# MySTM32F103C8.net
KiCad netlist of a schematic drawn in Altium Designer
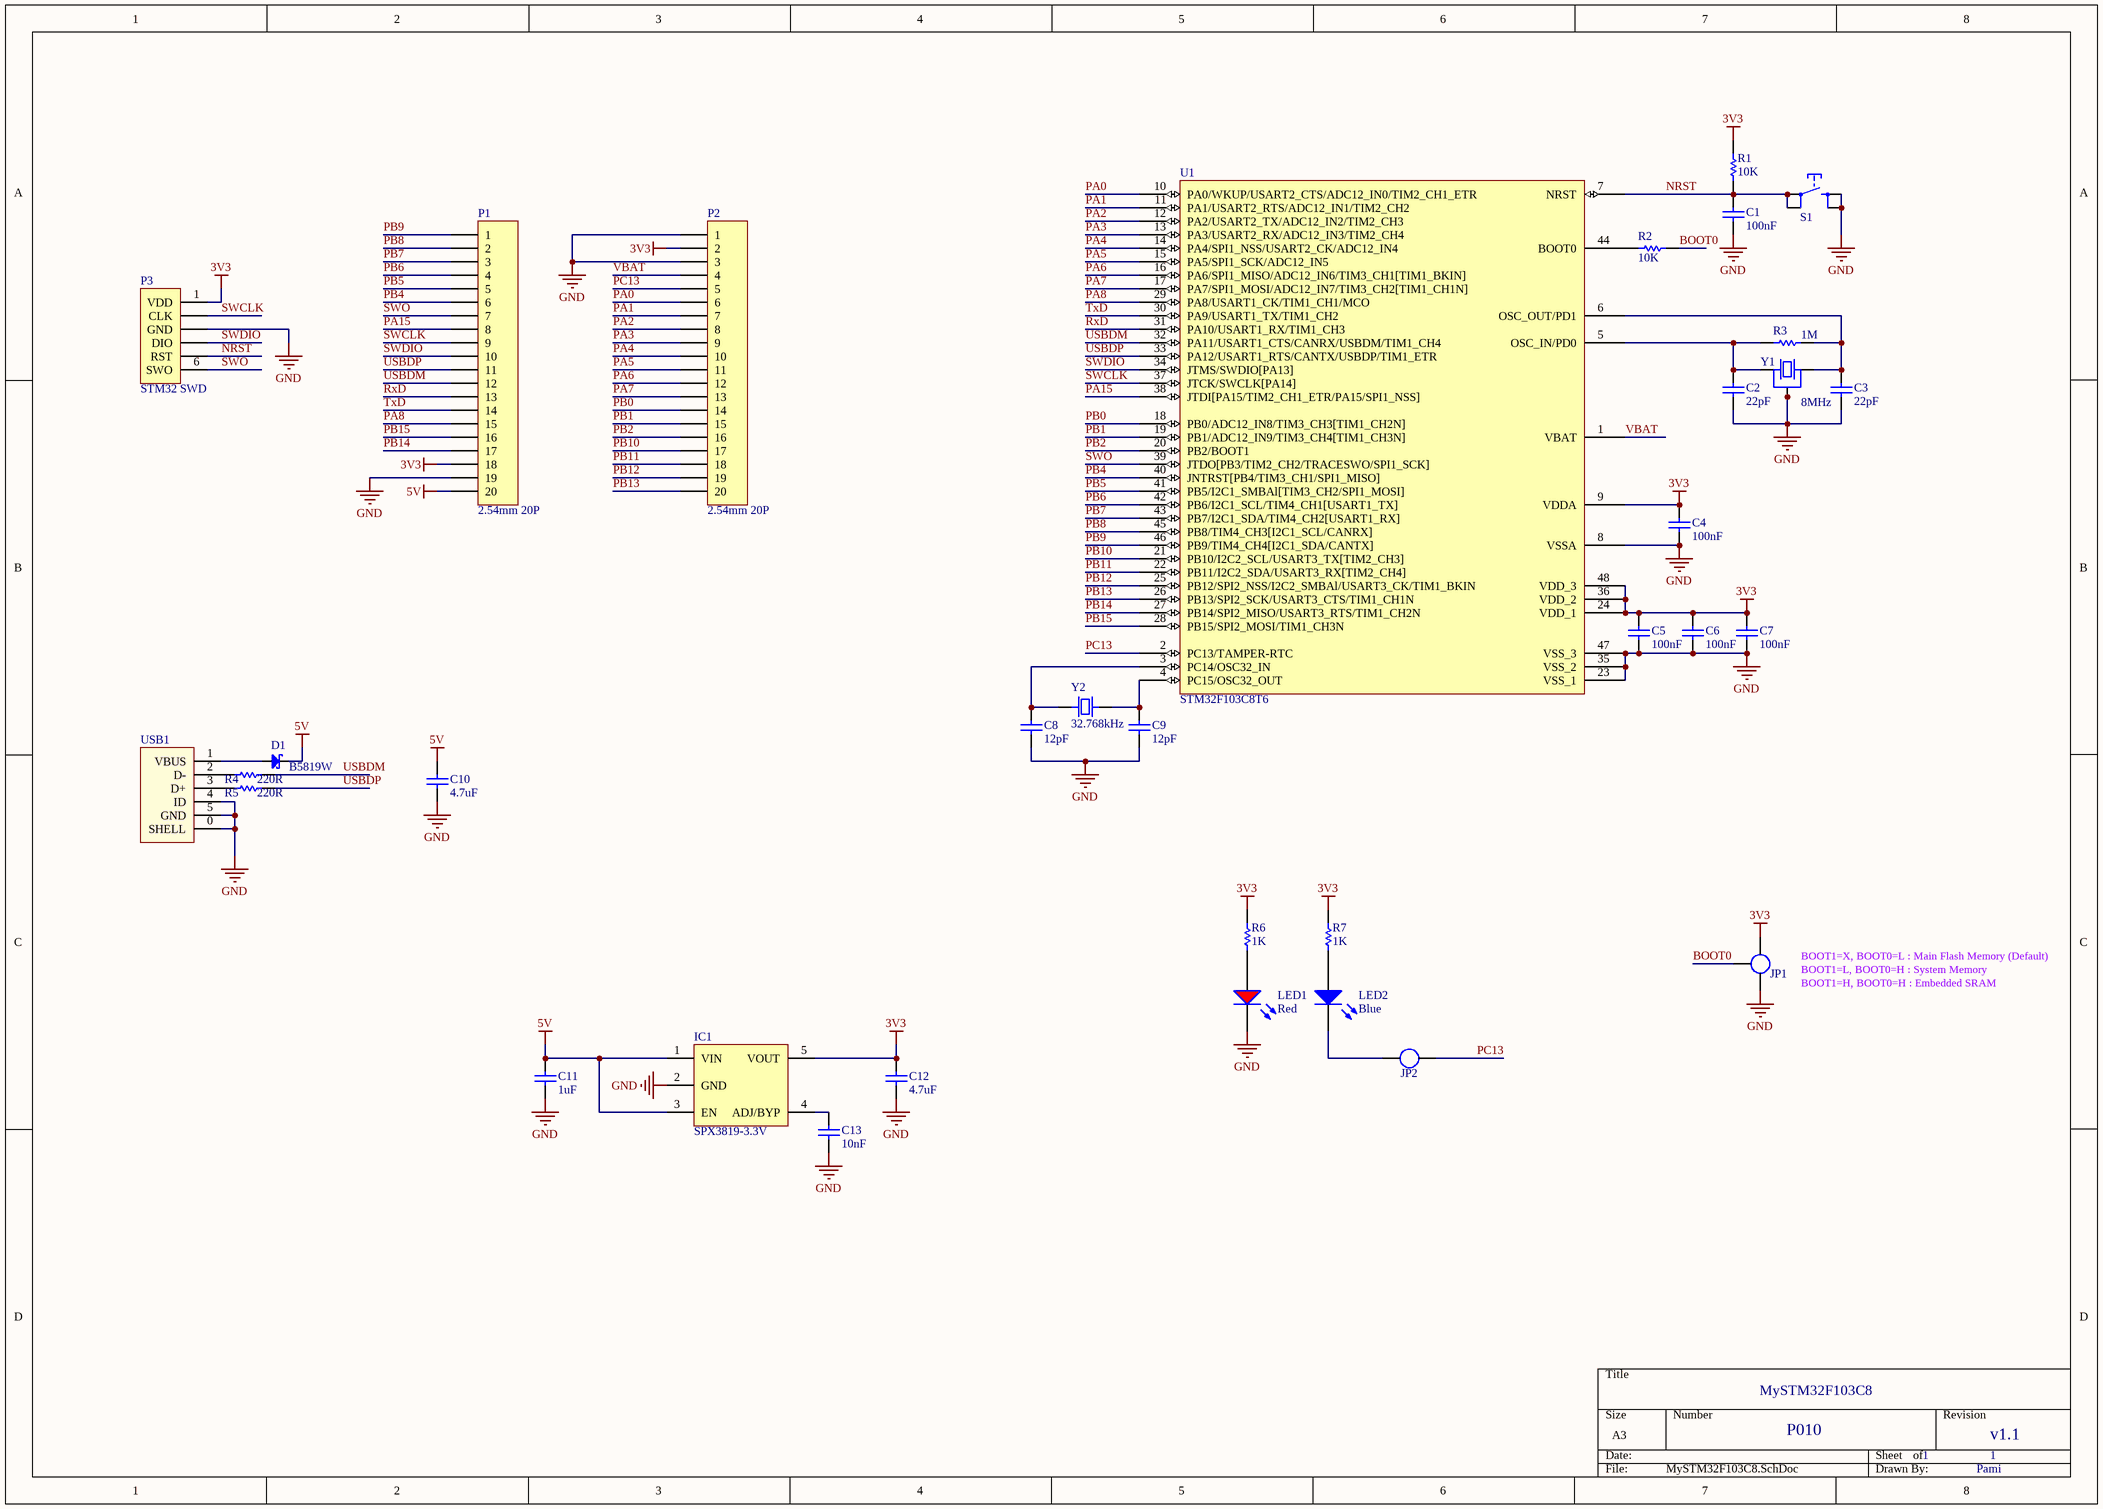
[diagram p0: MySTM32F103C8.SchDoc]

(export (version "E")
  (design (tool "Eeschema 10.0.6"))
  (components
    (comp (ref "C1")
      (value "100nF")
      (footprint "SMD-CAP-0402")
      (description "贴片电容")
      (fields
        (field (name "TOLERANCE") "±10%")
        (field (name "MANUFACTURER") "FengHua, YAGEO, Samsung, TDK, Murata")
      )
      (libsource (lib "My Capacitors") (part "0402 100nF (104) 10% 16V X7R"))
    )
    (comp (ref "C2")
      (value "22pF")
      (footprint "SMD-CAP-0402")
      (description "贴片电容")
      (fields
        (field (name "TOLERANCE") "±5%")
        (field (name "MANUFACTURER") "FengHua, YAGEO, Samsung, TDK, Murata")
      )
      (libsource (lib "My Capacitors") (part "0402 22pF (220) 5% 50V COG"))
    )
    (comp (ref "C3")
      (value "22pF")
      (footprint "SMD-CAP-0402")
      (description "贴片电容")
      (fields
        (field (name "TOLERANCE") "±5%")
        (field (name "MANUFACTURER") "FengHua, YAGEO, Samsung, TDK, Murata")
      )
      (libsource (lib "My Capacitors") (part "0402 22pF (220) 5% 50V COG"))
    )
    (comp (ref "C4")
      (value "100nF")
      (footprint "SMD-CAP-0402")
      (description "贴片电容")
      (fields
        (field (name "TOLERANCE") "±10%")
        (field (name "MANUFACTURER") "FengHua, YAGEO, Samsung, TDK, Murata")
      )
      (libsource (lib "My Capacitors") (part "0402 100nF (104) 10% 16V X7R"))
    )
    (comp (ref "C5")
      (value "100nF")
      (footprint "SMD-CAP-0402")
      (description "贴片电容")
      (fields
        (field (name "TOLERANCE") "±10%")
        (field (name "MANUFACTURER") "FengHua, YAGEO, Samsung, TDK, Murata")
      )
      (libsource (lib "My Capacitors") (part "0402 100nF (104) 10% 16V X7R"))
    )
    (comp (ref "C6")
      (value "100nF")
      (footprint "SMD-CAP-0402")
      (description "贴片电容")
      (fields
        (field (name "TOLERANCE") "±10%")
        (field (name "MANUFACTURER") "FengHua, YAGEO, Samsung, TDK, Murata")
      )
      (libsource (lib "My Capacitors") (part "0402 100nF (104) 10% 16V X7R"))
    )
    (comp (ref "C7")
      (value "100nF")
      (footprint "SMD-CAP-0402")
      (description "贴片电容")
      (fields
        (field (name "TOLERANCE") "±10%")
        (field (name "MANUFACTURER") "FengHua, YAGEO, Samsung, TDK, Murata")
      )
      (libsource (lib "My Capacitors") (part "0402 100nF (104) 10% 16V X7R"))
    )
    (comp (ref "C8")
      (value "12pF")
      (footprint "SMD-CAP-0402")
      (description "贴片电容")
      (fields
        (field (name "TOLERANCE") "±5%")
        (field (name "MANUFACTURER") "FengHua, YAGEO, Samsung, TDK, Murata")
      )
      (libsource (lib "My Capacitors") (part "0402 12pF (120) 5% 50V COG"))
    )
    (comp (ref "C9")
      (value "12pF")
      (footprint "SMD-CAP-0402")
      (description "贴片电容")
      (fields
        (field (name "TOLERANCE") "±5%")
        (field (name "MANUFACTURER") "FengHua, YAGEO, Samsung, TDK, Murata")
      )
      (libsource (lib "My Capacitors") (part "0402 12pF (120) 5% 50V COG"))
    )
    (comp (ref "C10")
      (value "4.7uF")
      (footprint "SMD-CAP-0603")
      (description "贴片电容")
      (fields
        (field (name "TOLERANCE") "±10%")
        (field (name "MANUFACTURER") "FengHua, YAGEO, Samsung, TDK, Murata")
      )
      (libsource (lib "My Capacitors") (part "0603 4.7uF (475) 10% 10V X5R"))
    )
    (comp (ref "C11")
      (value "1uF")
      (footprint "SMD-CAP-0402")
      (description "贴片电容")
      (fields
        (field (name "TOLERANCE") "±10%")
        (field (name "MANUFACTURER") "FengHua, YAGEO, Samsung, TDK, Murata")
      )
      (libsource (lib "My Capacitors") (part "0402 1uF(105) 10% 16V X5R"))
    )
    (comp (ref "C12")
      (value "4.7uF")
      (footprint "SMD-CAP-0603")
      (description "贴片电容")
      (fields
        (field (name "TOLERANCE") "±10%")
        (field (name "MANUFACTURER") "FengHua, YAGEO, Samsung, TDK, Murata")
      )
      (libsource (lib "My Capacitors") (part "0603 4.7uF (475) 10% 10V X5R"))
    )
    (comp (ref "C13")
      (value "10nF")
      (footprint "SMD-CAP-0402")
      (description "贴片电容")
      (fields
        (field (name "TOLERANCE") "±10%")
        (field (name "MANUFACTURER") "FengHua, YAGEO, Samsung, TDK, Murata")
      )
      (libsource (lib "My Capacitors") (part "0402 10nF (103) 10% 50V X7R"))
    )
    (comp (ref "D1")
      (value "B5819W")
      (footprint "SOD-123")
      (description "贴片二极管")
      (libsource (lib "My Diodes") (part "B5819W 40V/1A"))
    )
    (comp (ref "IC1")
      (value "SPX3819-3.3V")
      (footprint "SOT-23-5")
      (description "贴片LDO")
      (fields (field (name "MANUFACTURER") "EXAR") (field (name "TOLERANCE") "1%"))
      (libsource (lib "My LDO") (part "SPX3819M5 3.3V 500mA"))
    )
    (comp (ref "JP1")
      (value "JP-3P-P")
      (footprint "SMD-JUMPER-3-PASTE")
      (libsource (lib "My Jumpers") (part "JP-3P-P"))
    )
    (comp (ref "JP2")
      (value "JP-2P-P")
      (footprint "SMD-JUMPER-2-PASTE")
      (libsource (lib "My Jumpers") (part "JP-2P-P"))
    )
    (comp (ref "LED1")
      (value "Red")
      (footprint "SMD-LED-0603-RED")
      (description "贴片LED")
      (libsource (lib "My LED") (part "0603 Red"))
    )
    (comp (ref "LED2")
      (value "Blue")
      (footprint "SMD-LED-0603-BLUE")
      (description "贴片LED")
      (libsource (lib "My LED") (part "0603 Blue"))
    )
    (comp (ref "P1")
      (value "2.54mm 20P")
      (footprint "PSH1x20")
      (description "直插式连接器 2.54mm")
      (libsource (lib "My Connectors") (part "PSH Header 2.54mm 20P"))
    )
    (comp (ref "P2")
      (value "2.54mm 20P")
      (footprint "PSH1x20")
      (description "直插式连接器 2.54mm")
      (libsource (lib "My Connectors") (part "PSH Header 2.54mm 20P"))
    )
    (comp (ref "P3")
      (value "STM32 SWD")
      (footprint "STM32-SWD-PTH-6-2.45")
      (description "调试端口")
      (libsource (lib "My Connectors") (part "STM32 SWD6 PTH 2.54mm"))
    )
    (comp (ref "R1")
      (value "10K")
      (footprint "SMD-RES-0402")
      (description "贴片电阻")
      (fields
        (field (name "MANUFACTURER") "FengHua, YAGEO, RALEC, KOA, ROHM")
        (field (name "TOLERANCE") "±1%")
      )
      (libsource (lib "My Resistors") (part "0402 10KΩ (1002) 1% 1/16W"))
    )
    (comp (ref "R2")
      (value "10K")
      (footprint "SMD-RES-0402")
      (description "贴片电阻")
      (fields
        (field (name "MANUFACTURER") "FengHua, YAGEO, RALEC, KOA, ROHM")
        (field (name "TOLERANCE") "±1%")
      )
      (libsource (lib "My Resistors") (part "0402 10KΩ (1002) 1% 1/16W"))
    )
    (comp (ref "R3")
      (value "1M")
      (footprint "SMD-RES-0402")
      (description "贴片电阻")
      (fields
        (field (name "MANUFACTURER") "FengHua, YAGEO, RALEC, KOA, ROHM")
        (field (name "TOLERANCE") "±1%")
      )
      (libsource (lib "My Resistors") (part "0402 1MΩ (1004) 1% 1/16W"))
    )
    (comp (ref "R4")
      (value "220R")
      (footprint "SMD-RES-0402")
      (description "贴片电阻")
      (fields
        (field (name "MANUFACTURER") "FengHua, YAGEO, RALEC, KOA, ROHM")
        (field (name "TOLERANCE") "±1%")
      )
      (libsource (lib "My Resistors") (part "0402 220Ω (2200) 1% 1/16W"))
    )
    (comp (ref "R5")
      (value "220R")
      (footprint "SMD-RES-0402")
      (description "贴片电阻")
      (fields
        (field (name "MANUFACTURER") "FengHua, YAGEO, RALEC, KOA, ROHM")
        (field (name "TOLERANCE") "±1%")
      )
      (libsource (lib "My Resistors") (part "0402 220Ω (2200) 1% 1/16W"))
    )
    (comp (ref "R6")
      (value "1K")
      (footprint "SMD-RES-0402")
      (description "贴片电阻")
      (fields
        (field (name "MANUFACTURER") "FengHua, YAGEO, RALEC, KOA, ROHM")
        (field (name "TOLERANCE") "±1%")
      )
      (libsource (lib "My Resistors") (part "0402 1KΩ (1001) 1% 1/16W"))
    )
    (comp (ref "R7")
      (value "1K")
      (footprint "SMD-RES-0402")
      (description "贴片电阻")
      (fields
        (field (name "MANUFACTURER") "FengHua, YAGEO, RALEC, KOA, ROHM")
        (field (name "TOLERANCE") "±1%")
      )
      (libsource (lib "My Resistors") (part "0402 1KΩ (1001) 1% 1/16W"))
    )
    (comp (ref "S1")
      (value "Tact Switch 4x4")
      (footprint "SMD-SW-4x4")
      (description "轻触开关")
      (libsource (lib "My TactSwitch") (part "Tact Switch 4x4"))
    )
    (comp (ref "U1")
      (value "STM32F103C8T6")
      (footprint "LQFP48")
      (description "贴片 STM32 MCU")
      (libsource (lib "My Microcontrollers") (part "STM32F103C8T6"))
    )
    (comp (ref "USB1")
      (value "MicroUSB")
      (footprint "MICRO-USB-5P4S")
      (description "贴片USB母座")
      (fields (field (name "PART NUMBER") "614105150721") (field (name "PUBLISHER") "Wurth Elektronik"))
      (libsource (lib "My USB") (part "MicroUSB 5P 无卷边"))
    )
    (comp (ref "Y1")
      (value "8MHz")
      (footprint "OSC-3225")
      (description "贴片无源晶振")
      (libsource (lib "My Crystal oscillator") (part "3225 8MHz ±10ppm 10pF"))
    )
    (comp (ref "Y2")
      (value "32.768kHz")
      (footprint "OSC-FC-135")
      (description "贴片晶振")
      (fields (field (name "MANUFACTURER") "EPSON"))
      (libsource (lib "My Crystal oscillator") (part "3215 32.768kHz ±20ppm 12.5pF"))
    )
  )
  (nets
    (net (code "1") (name "/BOOT0") (class "Default")
      (node (ref "JP1") (pin "2") (pinfunction "2_2") (pintype "passive"))
      (node (ref "R2") (pin "1") (pinfunction "1_1") (pintype "passive"))
    )
    (net (code "2") (name "/NRST") (class "Default")
      (node (ref "C1") (pin "2") (pinfunction "2_2") (pintype "passive"))
      (node (ref "P3") (pin "5") (pinfunction "RST_5") (pintype "passive"))
      (node (ref "R1") (pin "1") (pinfunction "1_1") (pintype "passive"))
      (node (ref "S1") (pin "1") (pinfunction "1_1") (pintype "passive"))
      (node (ref "S1") (pin "2") (pinfunction "2_2") (pintype "passive"))
      (node (ref "U1") (pin "7") (pinfunction "NRST_7") (pintype "bidirectional"))
    )
    (net (code "3") (name "/PA0") (class "Default")
      (node (ref "P2") (pin "6") (pinfunction "6_6") (pintype "passive"))
      (node (ref "U1") (pin "10") (pinfunction "PA0/WKUP/USART2_CTS/ADC12_IN0/TIM2_CH1_ETR_10") (pintype "bidirectional"))
    )
    (net (code "4") (name "/PA1") (class "Default")
      (node (ref "P2") (pin "7") (pinfunction "7_7") (pintype "passive"))
      (node (ref "U1") (pin "11") (pinfunction "PA1/USART2_RTS/ADC12_IN1/TIM2_CH2_11") (pintype "bidirectional"))
    )
    (net (code "5") (name "/PA2") (class "Default")
      (node (ref "P2") (pin "8") (pinfunction "8_8") (pintype "passive"))
      (node (ref "U1") (pin "12") (pinfunction "PA2/USART2_TX/ADC12_IN2/TIM2_CH3_12") (pintype "bidirectional"))
    )
    (net (code "6") (name "/PA3") (class "Default")
      (node (ref "P2") (pin "9") (pinfunction "9_9") (pintype "passive"))
      (node (ref "U1") (pin "13") (pinfunction "PA3/USART2_RX/ADC12_IN3/TIM2_CH4_13") (pintype "bidirectional"))
    )
    (net (code "7") (name "/PA4") (class "Default")
      (node (ref "P2") (pin "10") (pinfunction "10_10") (pintype "passive"))
      (node (ref "U1") (pin "14") (pinfunction "PA4/SPI1_NSS/USART2_CK/ADC12_IN4_14") (pintype "bidirectional"))
    )
    (net (code "8") (name "/PA5") (class "Default")
      (node (ref "P2") (pin "11") (pinfunction "11_11") (pintype "passive"))
      (node (ref "U1") (pin "15") (pinfunction "PA5/SPI1_SCK/ADC12_IN5_15") (pintype "bidirectional"))
    )
    (net (code "9") (name "/PA6") (class "Default")
      (node (ref "P2") (pin "12") (pinfunction "12_12") (pintype "passive"))
      (node (ref "U1") (pin "16") (pinfunction "PA6/SPI1_MISO/ADC12_IN6/TIM3_CH1[TIM1_BKIN]_16") (pintype "bidirectional"))
    )
    (net (code "10") (name "/PA7") (class "Default")
      (node (ref "P2") (pin "13") (pinfunction "13_13") (pintype "passive"))
      (node (ref "U1") (pin "17") (pinfunction "PA7/SPI1_MOSI/ADC12_IN7/TIM3_CH2[TIM1_CH1N]_17") (pintype "bidirectional"))
    )
    (net (code "11") (name "/PA8") (class "Default")
      (node (ref "P1") (pin "15") (pinfunction "15_15") (pintype "passive"))
      (node (ref "U1") (pin "29") (pinfunction "PA8/USART1_CK/TIM1_CH1/MCO_29") (pintype "bidirectional"))
    )
    (net (code "12") (name "/PA15") (class "Default")
      (node (ref "P1") (pin "8") (pinfunction "8_8") (pintype "passive"))
      (node (ref "U1") (pin "38") (pinfunction "JTDI[PA15/TIM2_CH1_ETR/PA15/SPI1_NSS]_38") (pintype "bidirectional"))
    )
    (net (code "13") (name "/PB0") (class "Default")
      (node (ref "P2") (pin "14") (pinfunction "14_14") (pintype "passive"))
      (node (ref "U1") (pin "18") (pinfunction "PB0/ADC12_IN8/TIM3_CH3[TIM1_CH2N]_18") (pintype "bidirectional"))
    )
    (net (code "14") (name "/PB1") (class "Default")
      (node (ref "P2") (pin "15") (pinfunction "15_15") (pintype "passive"))
      (node (ref "U1") (pin "19") (pinfunction "PB1/ADC12_IN9/TIM3_CH4[TIM1_CH3N]_19") (pintype "bidirectional"))
    )
    (net (code "15") (name "/PB2") (class "Default")
      (node (ref "P2") (pin "16") (pinfunction "16_16") (pintype "passive"))
      (node (ref "U1") (pin "20") (pinfunction "PB2/BOOT1_20") (pintype "bidirectional"))
    )
    (net (code "16") (name "/PB4") (class "Default")
      (node (ref "P1") (pin "6") (pinfunction "6_6") (pintype "passive"))
      (node (ref "U1") (pin "40") (pinfunction "JNTRST[PB4/TIM3_CH1/SPI1_MISO]_40") (pintype "bidirectional"))
    )
    (net (code "17") (name "/PB5") (class "Default")
      (node (ref "P1") (pin "5") (pinfunction "5_5") (pintype "passive"))
      (node (ref "U1") (pin "41") (pinfunction "PB5/I2C1_SMBAl[TIM3_CH2/SPI1_MOSI]_41") (pintype "bidirectional"))
    )
    (net (code "18") (name "/PB6") (class "Default")
      (node (ref "P1") (pin "4") (pinfunction "4_4") (pintype "passive"))
      (node (ref "U1") (pin "42") (pinfunction "PB6/I2C1_SCL/TIM4_CH1[USART1_TX]_42") (pintype "bidirectional"))
    )
    (net (code "19") (name "/PB7") (class "Default")
      (node (ref "P1") (pin "3") (pinfunction "3_3") (pintype "passive"))
      (node (ref "U1") (pin "43") (pinfunction "PB7/I2C1_SDA/TIM4_CH2[USART1_RX]_43") (pintype "bidirectional"))
    )
    (net (code "20") (name "/PB8") (class "Default")
      (node (ref "P1") (pin "2") (pinfunction "2_2") (pintype "passive"))
      (node (ref "U1") (pin "45") (pinfunction "PB8/TIM4_CH3[I2C1_SCL/CANRX]_45") (pintype "bidirectional"))
    )
    (net (code "21") (name "/PB9") (class "Default")
      (node (ref "P1") (pin "1") (pinfunction "1_1") (pintype "passive"))
      (node (ref "U1") (pin "46") (pinfunction "PB9/TIM4_CH4[I2C1_SDA/CANTX]_46") (pintype "bidirectional"))
    )
    (net (code "22") (name "/PB10") (class "Default")
      (node (ref "P2") (pin "17") (pinfunction "17_17") (pintype "passive"))
      (node (ref "U1") (pin "21") (pinfunction "PB10/I2C2_SCL/USART3_TX[TIM2_CH3]_21") (pintype "bidirectional"))
    )
    (net (code "23") (name "/PB11") (class "Default")
      (node (ref "P2") (pin "18") (pinfunction "18_18") (pintype "passive"))
      (node (ref "U1") (pin "22") (pinfunction "PB11/I2C2_SDA/USART3_RX[TIM2_CH4]_22") (pintype "bidirectional"))
    )
    (net (code "24") (name "/PB12") (class "Default")
      (node (ref "P2") (pin "19") (pinfunction "19_19") (pintype "passive"))
      (node (ref "U1") (pin "25") (pinfunction "PB12/SPI2_NSS/I2C2_SMBAl/USART3_CK/TIM1_BKIN_25") (pintype "bidirectional"))
    )
    (net (code "25") (name "/PB13") (class "Default")
      (node (ref "P2") (pin "20") (pinfunction "20_20") (pintype "passive"))
      (node (ref "U1") (pin "26") (pinfunction "PB13/SPI2_SCK/USART3_CTS/TIM1_CH1N_26") (pintype "bidirectional"))
    )
    (net (code "26") (name "/PB14") (class "Default")
      (node (ref "P1") (pin "17") (pinfunction "17_17") (pintype "passive"))
      (node (ref "U1") (pin "27") (pinfunction "PB14/SPI2_MISO/USART3_RTS/TIM1_CH2N_27") (pintype "bidirectional"))
    )
    (net (code "27") (name "/PB15") (class "Default")
      (node (ref "P1") (pin "16") (pinfunction "16_16") (pintype "passive"))
      (node (ref "U1") (pin "28") (pinfunction "PB15/SPI2_MOSI/TIM1_CH3N_28") (pintype "bidirectional"))
    )
    (net (code "28") (name "/PC13") (class "Default")
      (node (ref "JP2") (pin "2") (pinfunction "2_2") (pintype "passive"))
      (node (ref "P2") (pin "5") (pinfunction "5_5") (pintype "passive"))
      (node (ref "U1") (pin "2") (pinfunction "PC13/TAMPER-RTC_2") (pintype "bidirectional"))
    )
    (net (code "29") (name "/RxD") (class "Default")
      (node (ref "P1") (pin "13") (pinfunction "13_13") (pintype "passive"))
      (node (ref "U1") (pin "31") (pinfunction "PA10/USART1_RX/TIM1_CH3_31") (pintype "bidirectional"))
    )
    (net (code "30") (name "/SWCLK") (class "Default")
      (node (ref "P1") (pin "9") (pinfunction "9_9") (pintype "passive"))
      (node (ref "P3") (pin "2") (pinfunction "CLK_2") (pintype "passive"))
      (node (ref "U1") (pin "37") (pinfunction "JTCK/SWCLK[PA14]_37") (pintype "bidirectional"))
    )
    (net (code "31") (name "/SWDIO") (class "Default")
      (node (ref "P1") (pin "10") (pinfunction "10_10") (pintype "passive"))
      (node (ref "P3") (pin "4") (pinfunction "DIO_4") (pintype "power_in"))
      (node (ref "U1") (pin "34") (pinfunction "JTMS/SWDIO[PA13]_34") (pintype "bidirectional"))
    )
    (net (code "32") (name "/SWO") (class "Default")
      (node (ref "P1") (pin "7") (pinfunction "7_7") (pintype "passive"))
      (node (ref "P3") (pin "6") (pinfunction "SWO_6") (pintype "passive"))
      (node (ref "U1") (pin "39") (pinfunction "JTDO[PB3/TIM2_CH2/TRACESWO/SPI1_SCK]_39") (pintype "bidirectional"))
    )
    (net (code "33") (name "/TxD") (class "Default")
      (node (ref "P1") (pin "14") (pinfunction "14_14") (pintype "passive"))
      (node (ref "U1") (pin "30") (pinfunction "PA9/USART1_TX/TIM1_CH2_30") (pintype "bidirectional"))
    )
    (net (code "34") (name "/USBDM") (class "Default")
      (node (ref "P1") (pin "12") (pinfunction "12_12") (pintype "passive"))
      (node (ref "R4") (pin "2") (pinfunction "2_2") (pintype "passive"))
      (node (ref "U1") (pin "32") (pinfunction "PA11/USART1_CTS/CANRX/USBDM/TIM1_CH4_32") (pintype "bidirectional"))
    )
    (net (code "35") (name "/USBDP") (class "Default")
      (node (ref "P1") (pin "11") (pinfunction "11_11") (pintype "passive"))
      (node (ref "R5") (pin "2") (pinfunction "2_2") (pintype "passive"))
      (node (ref "U1") (pin "33") (pinfunction "PA12/USART1_RTS/CANTX/USBDP/TIM1_ETR_33") (pintype "bidirectional"))
    )
    (net (code "36") (name "/VBAT") (class "Default")
      (node (ref "P2") (pin "4") (pinfunction "4_4") (pintype "passive"))
      (node (ref "U1") (pin "1") (pinfunction "VBAT_1") (pintype "power_in"))
    )
    (net (code "37") (name "3V3") (class "Default")
      (node (ref "C12") (pin "2") (pinfunction "2_2") (pintype "passive"))
      (node (ref "C4") (pin "2") (pinfunction "2_2") (pintype "passive"))
      (node (ref "C5") (pin "2") (pinfunction "2_2") (pintype "passive"))
      (node (ref "C6") (pin "2") (pinfunction "2_2") (pintype "passive"))
      (node (ref "C7") (pin "2") (pinfunction "2_2") (pintype "passive"))
      (node (ref "IC1") (pin "5") (pinfunction "VOUT_5") (pintype "power_in"))
      (node (ref "JP1") (pin "1") (pinfunction "1_1") (pintype "passive"))
      (node (ref "P1") (pin "18") (pinfunction "18_18") (pintype "passive"))
      (node (ref "P2") (pin "2") (pinfunction "2_2") (pintype "passive"))
      (node (ref "P3") (pin "1") (pinfunction "VDD_1") (pintype "power_in"))
      (node (ref "R1") (pin "2") (pinfunction "2_2") (pintype "passive"))
      (node (ref "R6") (pin "2") (pinfunction "2_2") (pintype "passive"))
      (node (ref "R7") (pin "2") (pinfunction "2_2") (pintype "passive"))
      (node (ref "U1") (pin "24") (pinfunction "VDD_1_24") (pintype "power_in"))
      (node (ref "U1") (pin "36") (pinfunction "VDD_2_36") (pintype "power_in"))
      (node (ref "U1") (pin "48") (pinfunction "VDD_3_48") (pintype "power_in"))
      (node (ref "U1") (pin "9") (pinfunction "VDDA_9") (pintype "power_in"))
    )
    (net (code "38") (name "5V") (class "Default")
      (node (ref "C10") (pin "2") (pinfunction "2_2") (pintype "passive"))
      (node (ref "C11") (pin "2") (pinfunction "2_2") (pintype "passive"))
      (node (ref "D1") (pin "1") (pinfunction "K_1") (pintype "passive"))
      (node (ref "IC1") (pin "1") (pinfunction "VIN_1") (pintype "power_in"))
      (node (ref "IC1") (pin "3") (pinfunction "EN_3") (pintype "passive"))
      (node (ref "P1") (pin "20") (pinfunction "20_20") (pintype "passive"))
    )
    (net (code "39") (name "GND") (class "Default")
      (node (ref "C1") (pin "1") (pinfunction "1_1") (pintype "passive"))
      (node (ref "C10") (pin "1") (pinfunction "1_1") (pintype "passive"))
      (node (ref "C11") (pin "1") (pinfunction "1_1") (pintype "passive"))
      (node (ref "C12") (pin "1") (pinfunction "1_1") (pintype "passive"))
      (node (ref "C13") (pin "1") (pinfunction "1_1") (pintype "passive"))
      (node (ref "C2") (pin "1") (pinfunction "1_1") (pintype "passive"))
      (node (ref "C3") (pin "1") (pinfunction "1_1") (pintype "passive"))
      (node (ref "C4") (pin "1") (pinfunction "1_1") (pintype "passive"))
      (node (ref "C5") (pin "1") (pinfunction "1_1") (pintype "passive"))
      (node (ref "C6") (pin "1") (pinfunction "1_1") (pintype "passive"))
      (node (ref "C7") (pin "1") (pinfunction "1_1") (pintype "passive"))
      (node (ref "C8") (pin "1") (pinfunction "1_1") (pintype "passive"))
      (node (ref "C9") (pin "1") (pinfunction "1_1") (pintype "passive"))
      (node (ref "IC1") (pin "2") (pinfunction "GND_2") (pintype "power_in"))
      (node (ref "JP1") (pin "3") (pinfunction "3_3") (pintype "passive"))
      (node (ref "LED1") (pin "2") (pinfunction "K_2") (pintype "passive"))
      (node (ref "P1") (pin "19") (pinfunction "19_19") (pintype "passive"))
      (node (ref "P2") (pin "1") (pinfunction "1_1") (pintype "passive"))
      (node (ref "P2") (pin "3") (pinfunction "3_3") (pintype "passive"))
      (node (ref "P3") (pin "3") (pinfunction "GND_3") (pintype "passive"))
      (node (ref "S1") (pin "3") (pinfunction "3_3") (pintype "passive"))
      (node (ref "S1") (pin "4") (pinfunction "4_4") (pintype "passive"))
      (node (ref "U1") (pin "23") (pinfunction "VSS_1_23") (pintype "power_in"))
      (node (ref "U1") (pin "35") (pinfunction "VSS_2_35") (pintype "power_in"))
      (node (ref "U1") (pin "47") (pinfunction "VSS_3_47") (pintype "power_in"))
      (node (ref "U1") (pin "8") (pinfunction "VSSA_8") (pintype "power_in"))
      (node (ref "USB1") (pin "0") (pinfunction "SHELL_0") (pintype "passive"))
      (node (ref "USB1") (pin "4") (pinfunction "ID_4") (pintype "passive"))
      (node (ref "USB1") (pin "5") (pinfunction "GND_5") (pintype "passive"))
      (node (ref "Y1") (pin "2") (pinfunction "2_2") (pintype "power_in"))
      (node (ref "Y1") (pin "4") (pinfunction "4_4") (pintype "passive"))
    )
    (net (code "40") (name "Net-(D1-A)") (class "Default")
      (node (ref "D1") (pin "2") (pinfunction "A_2") (pintype "passive"))
      (node (ref "USB1") (pin "1") (pinfunction "VBUS_1") (pintype "passive"))
    )
    (net (code "41") (name "Net-(IC1-ADJ{slash}BYP)") (class "Default")
      (node (ref "C13") (pin "2") (pinfunction "2_2") (pintype "passive"))
      (node (ref "IC1") (pin "4") (pinfunction "ADJ/BYP_4") (pintype "passive"))
    )
    (net (code "42") (name "Net-(LED1-A)") (class "Default")
      (node (ref "LED1") (pin "1") (pinfunction "A_1") (pintype "passive"))
      (node (ref "R6") (pin "1") (pinfunction "1_1") (pintype "passive"))
    )
    (net (code "43") (name "Net-(LED2-A)") (class "Default")
      (node (ref "LED2") (pin "1") (pinfunction "A_1") (pintype "passive"))
      (node (ref "R7") (pin "1") (pinfunction "1_1") (pintype "passive"))
    )
    (net (code "44") (name "Net-(LED2-K)") (class "Default")
      (node (ref "JP2") (pin "1") (pinfunction "1_1") (pintype "passive"))
      (node (ref "LED2") (pin "2") (pinfunction "K_2") (pintype "passive"))
    )
    (net (code "45") (name "Net-(U1-BOOT0)") (class "Default")
      (node (ref "R2") (pin "2") (pinfunction "2_2") (pintype "passive"))
      (node (ref "U1") (pin "44") (pinfunction "BOOT0_44") (pintype "passive"))
    )
    (net (code "46") (name "Net-(U1-OSC_IN{slash}PD0)") (class "Default")
      (node (ref "C2") (pin "2") (pinfunction "2_2") (pintype "passive"))
      (node (ref "R3") (pin "1") (pinfunction "1_1") (pintype "passive"))
      (node (ref "U1") (pin "5") (pinfunction "OSC_IN/PD0_5") (pintype "passive"))
      (node (ref "Y1") (pin "1") (pinfunction "1_1") (pintype "passive"))
    )
    (net (code "47") (name "Net-(U1-OSC_OUT{slash}PD1)") (class "Default")
      (node (ref "C3") (pin "2") (pinfunction "2_2") (pintype "passive"))
      (node (ref "R3") (pin "2") (pinfunction "2_2") (pintype "passive"))
      (node (ref "U1") (pin "6") (pinfunction "OSC_OUT/PD1_6") (pintype "passive"))
      (node (ref "Y1") (pin "3") (pinfunction "3_3") (pintype "passive"))
    )
    (net (code "48") (name "Net-(U1-PC14{slash}OSC32_IN)") (class "Default")
      (node (ref "C8") (pin "2") (pinfunction "2_2") (pintype "passive"))
      (node (ref "U1") (pin "3") (pinfunction "PC14/OSC32_IN_3") (pintype "bidirectional"))
      (node (ref "Y2") (pin "1") (pinfunction "1_1") (pintype "passive"))
    )
    (net (code "49") (name "Net-(U1-PC15{slash}OSC32_OUT)") (class "Default")
      (node (ref "C9") (pin "2") (pinfunction "2_2") (pintype "passive"))
      (node (ref "U1") (pin "4") (pinfunction "PC15/OSC32_OUT_4") (pintype "bidirectional"))
      (node (ref "Y2") (pin "2") (pinfunction "2_2") (pintype "passive"))
    )
    (net (code "50") (name "Net-(USB1-D+)") (class "Default")
      (node (ref "R5") (pin "1") (pinfunction "1_1") (pintype "passive"))
      (node (ref "USB1") (pin "3") (pinfunction "D+_3") (pintype "passive"))
    )
    (net (code "51") (name "Net-(USB1-D-)") (class "Default")
      (node (ref "R4") (pin "1") (pinfunction "1_1") (pintype "passive"))
      (node (ref "USB1") (pin "2") (pinfunction "D-_2") (pintype "passive"))
    )
  )
)
